# EFNMR_POLARIZATION_V1.net
KiCad netlist of a schematic drawn in Altium Designer
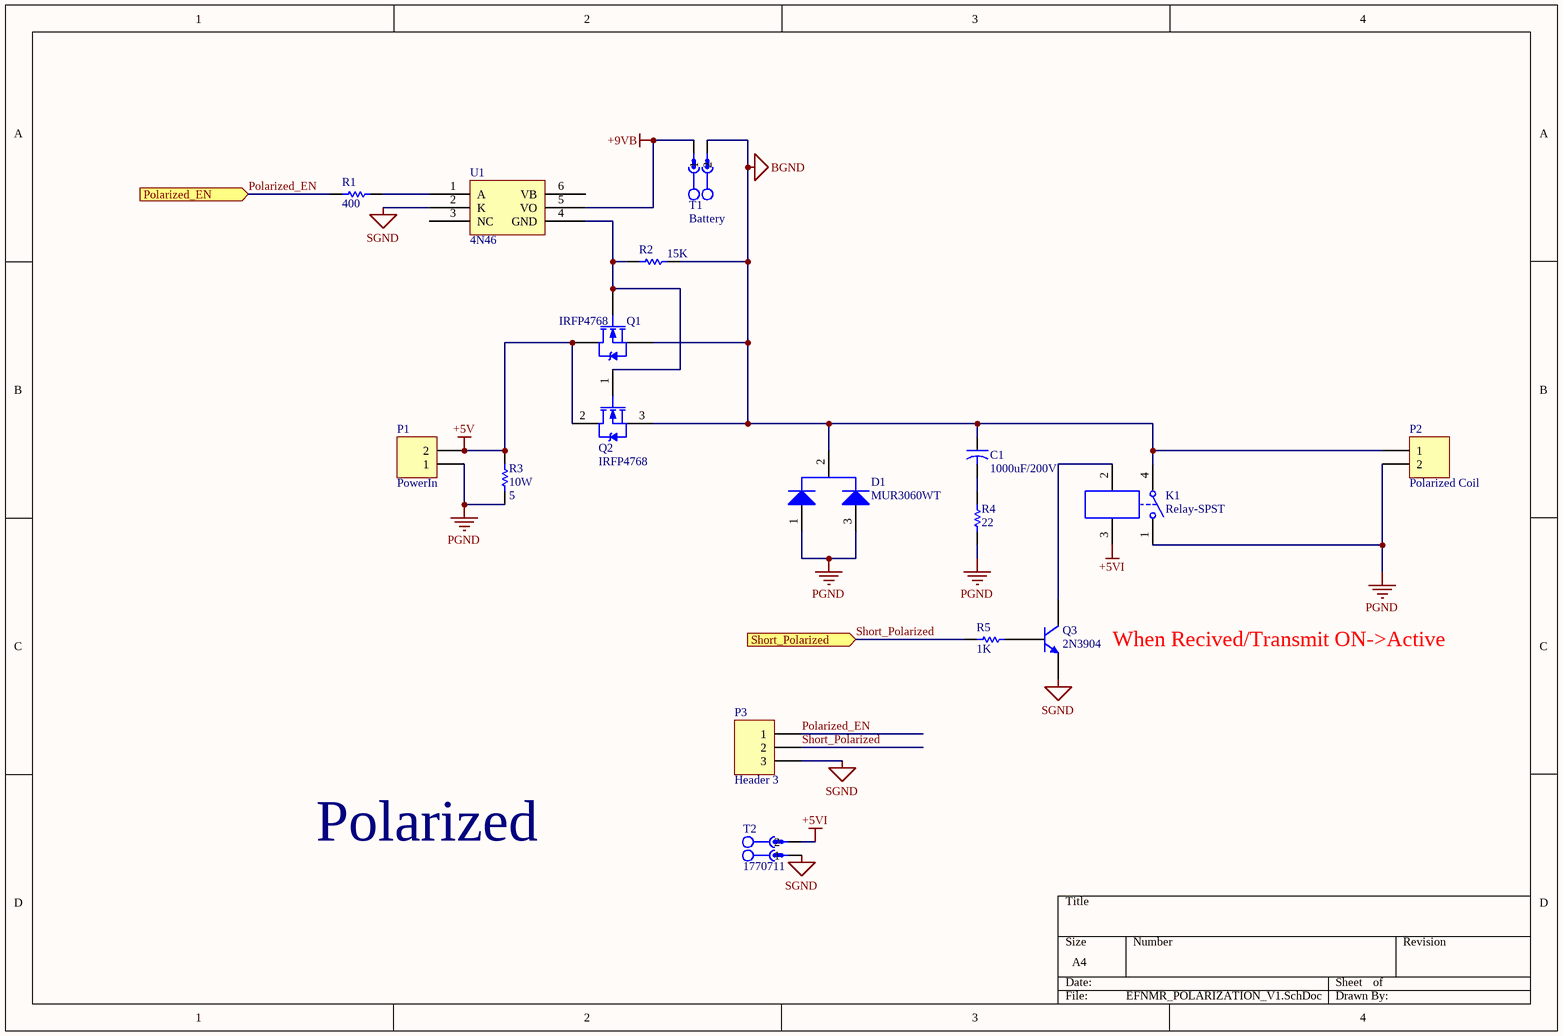
[diagram p0: EFNMR_POLARIZATION_V1.SchDoc]

(export (version "E")
  (design (tool "Eeschema 10.0.6"))
  (components
    (comp (ref "C1")
      (value "1000uF/200V")
      (footprint "Cap electrolitic radial 13x25-5")
      (description "Capacitor")
      (fields (field (name "PUBLISHER") "Altium Limited"))
      (libsource (lib "Miscellaneous Devices") (part "Cap2"))
    )
    (comp (ref "D1")
      (value "MUR3060WT")
      (footprint "TO-247AC")
      (description "SWITCHMODE(TM) Power Rectifier, 3-Pin TO-247, Tube")
      (fields (field (name "MANUFACTURER") "On Semiconductor"))
      (libsource (lib "ON Semi Rectifiers") (part "MUR3060WT"))
    )
    (comp (ref "K1")
      (value "Relay-SPST")
      (footprint "HE3351A0500")
      (description "Single-Pole Single-Throw Relay")
      (fields (field (name "PUBLISHER") "Altium Limited"))
      (libsource (lib "Miscellaneous Devices") (part "Relay-SPST"))
    )
    (comp (ref "P1")
      (value "PowerIn")
      (footprint "KF35C 2PIN")
      (description "Header, 2-Pin")
      (fields (field (name "PUBLISHER") "Altium Limited"))
      (libsource (lib "Miscellaneous Connectors") (part "Header 2"))
    )
    (comp (ref "P2")
      (value "Polarized Coil")
      (footprint "KF35C 2PIN")
      (description "Header, 2-Pin")
      (fields (field (name "PUBLISHER") "Altium Limited"))
      (libsource (lib "") (part "Header 2_1"))
    )
    (comp (ref "P3")
      (value "Header 3")
      (footprint "DS1070-3-COMCON")
      (description "Header, 3-Pin")
      (fields (field (name "PUBLISHER") "Altium Limited"))
      (libsource (lib "Miscellaneous Connectors") (part "Header 3"))
    )
    (comp (ref "Q1")
      (value "IRFP4768")
      (footprint "TO-247AC")
      (description "HEXFET Power MOSFET")
      (fields (field (name "PUBLISHER") "Altium Limited"))
      (libsource (lib "IR Discrete MOSFET - Power") (part "IRFP450"))
    )
    (comp (ref "Q2")
      (value "IRFP4768")
      (footprint "TO-247AC")
      (description "HEXFET Power MOSFET")
      (fields (field (name "PUBLISHER") "Altium Limited"))
      (libsource (lib "") (part "IRFP450_1"))
    )
    (comp (ref "Q3")
      (value "2N3904")
      (footprint "TO-92A")
      (description "NPN General Purpose Amplifier")
      (fields (field (name "PUBLISHER") "Altium Limited"))
      (libsource (lib "Miscellaneous Devices") (part "2N3904"))
    )
    (comp (ref "R1")
      (value "400")
      (footprint "Axial 0_25 W, 0_4 IN LEAD PITCH")
      (description "Resistor")
      (fields (field (name "PUBLISHER") "Altium Limited"))
      (libsource (lib "Miscellaneous Devices") (part "Res1"))
    )
    (comp (ref "R2")
      (value "15K")
      (footprint "Axial 0_25 W, 0_4 IN LEAD PITCH")
      (description "Resistor")
      (fields (field (name "PUBLISHER") "Altium Limited"))
      (libsource (lib "Miscellaneous Devices") (part "Res1"))
    )
    (comp (ref "R3")
      (value "10W")
      (footprint "Axial 3W 9_0mm")
      (description "Resistor")
      (fields (field (name "ALTIUM_VALUE") "5") (field (name "PUBLISHER") "Altium Limited"))
      (libsource (lib "Miscellaneous Devices") (part "Res1"))
    )
    (comp (ref "R4")
      (value "22")
      (footprint "Axial 1W  7_0mm")
      (description "Resistor")
      (fields (field (name "PUBLISHER") "Altium Limited"))
      (libsource (lib "Miscellaneous Devices") (part "Res1"))
    )
    (comp (ref "R5")
      (value "1K")
      (footprint "Axial 0_25 W, 0_4 IN LEAD PITCH")
      (description "Resistor")
      (fields (field (name "PUBLISHER") "Altium Limited"))
      (libsource (lib "Miscellaneous Devices") (part "Res1"))
    )
    (comp (ref "T1")
      (value "Battery")
      (footprint "MSTB 2,5/2-G-5,08")
      (description "2 Pitch: 5.08 mm Color: green Contact surface: Tin Assembly")
      (fields
        (field (name "MANUFACTURER") "PHOENIX CONTACT")
        (field (name "VOLTAGE") "320 V")
        (field (name "DESIGNER") "ABBAS BASEREH")
      )
      (libsource (lib "") (part "CON_Phoenix_MSTB_02_1"))
    )
    (comp (ref "T2")
      (value "1770711")
      (footprint "MSTB 2,5/2-G-5,08")
      (description "2 Pitch: 5.08 mm Color: green Contact surface: Tin Assembly")
      (fields
        (field (name "MANUFACTURER") "PHOENIX CONTACT")
        (field (name "VOLTAGE") "320 V")
        (field (name "DESIGNER") "ABBAS BASEREH")
      )
      (libsource (lib "Mofidi3D") (part "CON_Phoenix_MSTB_02"))
    )
    (comp (ref "U1")
      (value "4N46")
      (footprint "DIP-6")
      (description "Optocouplers")
      (libsource (lib "Mofidi3D") (part "4N46"))
    )
  )
  (nets
    (net (code "1") (name "+5V") (class "Default")
      (node (ref "P1") (pin "2") (pinfunction "2_2") (pintype "passive"))
      (node (ref "Q1") (pin "2") (pinfunction "D_2") (pintype "passive"))
      (node (ref "Q2") (pin "2") (pinfunction "D_2") (pintype "passive"))
      (node (ref "R3") (pin "2") (pinfunction "2_2") (pintype "passive"))
    )
    (net (code "2") (name "+5VI") (class "Default")
      (node (ref "K1") (pin "3") (pinfunction "3_3") (pintype "passive"))
      (node (ref "T2") (pin "2") (pinfunction "2_2") (pintype "passive"))
    )
    (net (code "3") (name "+9VB") (class "Default")
      (node (ref "T1") (pin "1") (pinfunction "1_1") (pintype "passive"))
      (node (ref "U1") (pin "5") (pinfunction "VO_5") (pintype "passive"))
    )
    (net (code "4") (name "/Polarized_EN") (class "Default")
      (node (ref "P3") (pin "1") (pinfunction "1_1") (pintype "passive"))
      (node (ref "R1") (pin "2") (pinfunction "2_2") (pintype "passive"))
    )
    (net (code "5") (name "/Short_Polarized") (class "Default")
      (node (ref "P3") (pin "2") (pinfunction "2_2") (pintype "passive"))
      (node (ref "R5") (pin "2") (pinfunction "2_2") (pintype "passive"))
    )
    (net (code "6") (name "BGND") (class "Default")
      (node (ref "C1") (pin "1") (pinfunction "1_1") (pintype "passive"))
      (node (ref "D1") (pin "2") (pinfunction "K_2") (pintype "passive"))
      (node (ref "K1") (pin "4") (pinfunction "4_4") (pintype "passive"))
      (node (ref "P2") (pin "1") (pinfunction "1_1") (pintype "passive"))
      (node (ref "Q1") (pin "3") (pinfunction "S_3") (pintype "passive"))
      (node (ref "Q2") (pin "3") (pinfunction "S_3") (pintype "passive"))
      (node (ref "R2") (pin "2") (pinfunction "2_2") (pintype "passive"))
      (node (ref "T1") (pin "2") (pinfunction "2_2") (pintype "passive"))
    )
    (net (code "7") (name "Net-(C1-Pad2)") (class "Default")
      (node (ref "C1") (pin "2") (pinfunction "2_2") (pintype "passive"))
      (node (ref "R4") (pin "2") (pinfunction "2_2") (pintype "passive"))
    )
    (net (code "8") (name "Net-(Q1-G)") (class "Default")
      (node (ref "Q1") (pin "1") (pinfunction "G_1") (pintype "passive"))
      (node (ref "Q2") (pin "1") (pinfunction "G_1") (pintype "passive"))
      (node (ref "R2") (pin "1") (pinfunction "1_1") (pintype "passive"))
      (node (ref "U1") (pin "4") (pinfunction "GND_4") (pintype "passive"))
    )
    (net (code "9") (name "Net-(Q3-B)") (class "Default")
      (node (ref "Q3") (pin "2") (pinfunction "B_2") (pintype "passive"))
      (node (ref "R5") (pin "1") (pinfunction "1_1") (pintype "passive"))
    )
    (net (code "10") (name "Net-(Q3-C)") (class "Default")
      (node (ref "K1") (pin "2") (pinfunction "2_2") (pintype "passive"))
      (node (ref "Q3") (pin "3") (pinfunction "C_3") (pintype "passive"))
    )
    (net (code "11") (name "Net-(U1-A)") (class "Default")
      (node (ref "R1") (pin "1") (pinfunction "1_1") (pintype "passive"))
      (node (ref "U1") (pin "1") (pinfunction "A_1") (pintype "passive"))
    )
    (net (code "12") (name "PGND") (class "Default")
      (node (ref "D1") (pin "1") (pinfunction "A1_1") (pintype "passive"))
      (node (ref "D1") (pin "3") (pinfunction "A2_3") (pintype "passive"))
      (node (ref "K1") (pin "1") (pinfunction "1_1") (pintype "passive"))
      (node (ref "P1") (pin "1") (pinfunction "1_1") (pintype "passive"))
      (node (ref "P2") (pin "2") (pinfunction "2_2") (pintype "passive"))
      (node (ref "R3") (pin "1") (pinfunction "1_1") (pintype "passive"))
      (node (ref "R4") (pin "1") (pinfunction "1_1") (pintype "passive"))
    )
    (net (code "13") (name "SGND") (class "Default")
      (node (ref "P3") (pin "3") (pinfunction "3_3") (pintype "passive"))
      (node (ref "Q3") (pin "1") (pinfunction "E_1") (pintype "passive"))
      (node (ref "T2") (pin "1") (pinfunction "1_1") (pintype "passive"))
      (node (ref "U1") (pin "2") (pinfunction "K_2") (pintype "passive"))
    )
    (net (code "14") (name "unconnected-(U1-NC-Pad3)") (class "Default")
      (node (ref "U1") (pin "3") (pinfunction "NC_3") (pintype "passive"))
    )
    (net (code "15") (name "unconnected-(U1-VB-Pad6)") (class "Default")
      (node (ref "U1") (pin "6") (pinfunction "VB_6") (pintype "passive"))
    )
  )
)
